# 05_PWMdriver.net
KiCad netlist of a schematic drawn in Altium Designer
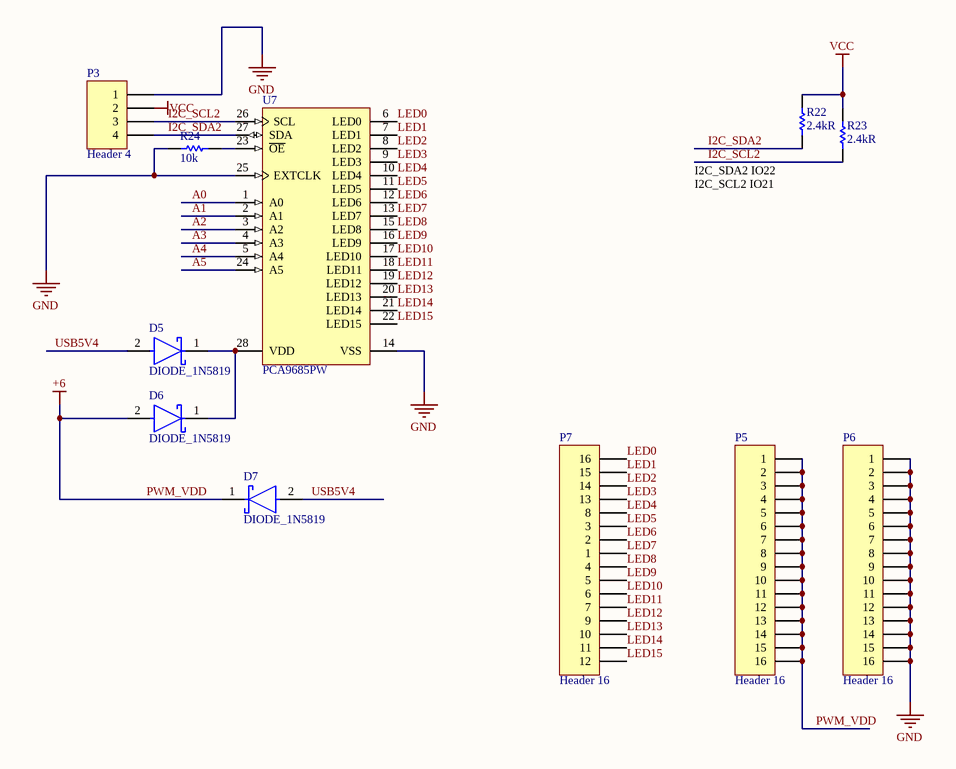
[diagram p0: 05_PWMdriver.SchDoc]

(export (version "E")
  (design (tool "Eeschema 10.0.6"))
  (components
    (comp (ref "D5")
      (value "DIODE_1N5819")
      (footprint "FP-SOD123-MFG")
      (description "DIODE SCHOTTKY 40V 1A SOD123")
      (fields
        (field (name "OCTOPART") "https://octopart.com/1n5819hw-7-f-diodes+inc.-323197")
        (field (name "MANUFACTURER") "Diodes Inc")
      )
      (libsource (lib "Altium Content Vault") (part "1d6ec82d83fb6aee721767c19dac4b9"))
    )
    (comp (ref "D6")
      (value "DIODE_1N5819")
      (footprint "FP-SOD123-MFG")
      (description "DIODE SCHOTTKY 40V 1A SOD123")
      (fields
        (field (name "OCTOPART") "https://octopart.com/1n5819hw-7-f-diodes+inc.-323197")
        (field (name "MANUFACTURER") "Diodes Inc")
      )
      (libsource (lib "Altium Content Vault") (part "1d6ec82d83fb6aee721767c19dac4b9"))
    )
    (comp (ref "D7")
      (value "DIODE_1N5819")
      (footprint "FP-SOD123-MFG")
      (description "DIODE SCHOTTKY 40V 1A SOD123")
      (fields
        (field (name "OCTOPART") "https://octopart.com/1n5819hw-7-f-diodes+inc.-323197")
        (field (name "MANUFACTURER") "Diodes Inc")
      )
      (libsource (lib "Altium Content Vault") (part "1d6ec82d83fb6aee721767c19dac4b9"))
    )
    (comp (ref "P3")
      (value "Header 4")
      (footprint "HDR1X4")
      (description "Header, 4-Pin")
      (fields (field (name "PUBLISHER") "Altium Limited"))
      (libsource (lib "Miscellaneous Connectors") (part "Header 4"))
    )
    (comp (ref "P5")
      (value "Header 16")
      (footprint "HDR1X16")
      (description "Header, 16-Pin")
      (fields (field (name "PUBLISHER") "Altium Limited"))
      (libsource (lib "Miscellaneous Connectors") (part "Header 16"))
    )
    (comp (ref "P6")
      (value "Header 16")
      (footprint "HDR1X16")
      (description "Header, 16-Pin")
      (fields (field (name "PUBLISHER") "Altium Limited"))
      (libsource (lib "Miscellaneous Connectors") (part "Header 16"))
    )
    (comp (ref "P7")
      (value "Header 16")
      (footprint "HDR1X16")
      (description "Header, 16-Pin")
      (fields (field (name "PUBLISHER") "Altium Limited"))
      (libsource (lib "") (part "Header 16_1"))
    )
    (comp (ref "R22")
      (value "2.4kR")
      (footprint "RESC1608X50X30ML20T20")
      (fields
        (field (name "PART NUMBER") "RR0816P-242-D")
        (field (name "MANUFACTURER") "Susumu")
        (field (name "Comment") "R0603_2.4K")
      )
      (libsource (lib "Altium Content Vault") (part "RES"))
    )
    (comp (ref "R23")
      (value "2.4kR")
      (footprint "RESC1608X50X30ML20T20")
      (fields
        (field (name "PART NUMBER") "RR0816P-242-D")
        (field (name "MANUFACTURER") "Susumu")
        (field (name "Comment") "R0603_2.4K")
      )
      (libsource (lib "Altium Content Vault") (part "RES"))
    )
    (comp (ref "R24")
      (value "10k")
      (footprint "RESC1609X55X30LL15T15")
      (description "Chip Resistor, 10 KOhm, +/- 1%, 0.1 W, -55 to 155 degC, 0603 (1608 Metric), RoHS, Tape and Reel")
      (fields (field (name "TOLERANCE") "1%") (field (name "MANUFACTURER") "Panasonic"))
      (libsource (lib "Altium Content Vault") (part "RES-2"))
    )
    (comp (ref "U7")
      (value "PCA9685PW")
      (footprint "SOT361-1_V")
      (fields (field (name "PARTNUMBER") "PCA9685"))
      (libsource (lib "Altium Content Vault") (part "NXP-PCA9685-SOT361-1"))
    )
  )
  (nets
    (net (code "1") (name "+6") (class "Default")
      (node (ref "D6") (pin "2") (pinfunction "A_2") (pintype "passive"))
      (node (ref "D7") (pin "1") (pinfunction "C_1") (pintype "passive"))
      (node (ref "P5") (pin "1") (pinfunction "1_1") (pintype "passive"))
      (node (ref "P5") (pin "10") (pinfunction "10_10") (pintype "passive"))
      (node (ref "P5") (pin "11") (pinfunction "11_11") (pintype "passive"))
      (node (ref "P5") (pin "12") (pinfunction "12_12") (pintype "passive"))
      (node (ref "P5") (pin "13") (pinfunction "13_13") (pintype "passive"))
      (node (ref "P5") (pin "14") (pinfunction "14_14") (pintype "passive"))
      (node (ref "P5") (pin "15") (pinfunction "15_15") (pintype "passive"))
      (node (ref "P5") (pin "16") (pinfunction "16_16") (pintype "passive"))
      (node (ref "P5") (pin "2") (pinfunction "2_2") (pintype "passive"))
      (node (ref "P5") (pin "3") (pinfunction "3_3") (pintype "passive"))
      (node (ref "P5") (pin "4") (pinfunction "4_4") (pintype "passive"))
      (node (ref "P5") (pin "5") (pinfunction "5_5") (pintype "passive"))
      (node (ref "P5") (pin "6") (pinfunction "6_6") (pintype "passive"))
      (node (ref "P5") (pin "7") (pinfunction "7_7") (pintype "passive"))
      (node (ref "P5") (pin "8") (pinfunction "8_8") (pintype "passive"))
      (node (ref "P5") (pin "9") (pinfunction "9_9") (pintype "passive"))
    )
    (net (code "2") (name "/A0") (class "Default")
      (node (ref "U7") (pin "1") (pinfunction "A0_1") (pintype "input"))
    )
    (net (code "3") (name "/A1") (class "Default")
      (node (ref "U7") (pin "2") (pinfunction "A1_2") (pintype "input"))
    )
    (net (code "4") (name "/A2") (class "Default")
      (node (ref "U7") (pin "3") (pinfunction "A2_3") (pintype "input"))
    )
    (net (code "5") (name "/A3") (class "Default")
      (node (ref "U7") (pin "4") (pinfunction "A3_4") (pintype "input"))
    )
    (net (code "6") (name "/A4") (class "Default")
      (node (ref "U7") (pin "5") (pinfunction "A4_5") (pintype "input"))
    )
    (net (code "7") (name "/A5") (class "Default")
      (node (ref "U7") (pin "24") (pinfunction "A5_24") (pintype "input"))
    )
    (net (code "8") (name "/I2C_SCL2") (class "Default")
      (node (ref "P3") (pin "3") (pinfunction "3_3") (pintype "passive"))
      (node (ref "R23") (pin "1") (pinfunction "1_1") (pintype "passive"))
      (node (ref "U7") (pin "26") (pinfunction "SCL_26") (pintype "input"))
    )
    (net (code "9") (name "/I2C_SDA2") (class "Default")
      (node (ref "P3") (pin "4") (pinfunction "4_4") (pintype "passive"))
      (node (ref "R22") (pin "1") (pinfunction "1_1") (pintype "passive"))
      (node (ref "U7") (pin "27") (pinfunction "SDA_27") (pintype "bidirectional"))
    )
    (net (code "10") (name "/LED0") (class "Default")
      (node (ref "P7") (pin "16") (pinfunction "16_16") (pintype "passive"))
      (node (ref "U7") (pin "6") (pinfunction "LED0_6") (pintype "tri_state"))
    )
    (net (code "11") (name "/LED1") (class "Default")
      (node (ref "P7") (pin "15") (pinfunction "15_15") (pintype "passive"))
      (node (ref "U7") (pin "7") (pinfunction "LED1_7") (pintype "tri_state"))
    )
    (net (code "12") (name "/LED2") (class "Default")
      (node (ref "P7") (pin "14") (pinfunction "14_14") (pintype "passive"))
      (node (ref "U7") (pin "8") (pinfunction "LED2_8") (pintype "tri_state"))
    )
    (net (code "13") (name "/LED3") (class "Default")
      (node (ref "P7") (pin "13") (pinfunction "13_13") (pintype "passive"))
      (node (ref "U7") (pin "9") (pinfunction "LED3_9") (pintype "tri_state"))
    )
    (net (code "14") (name "/LED4") (class "Default")
      (node (ref "P7") (pin "8") (pinfunction "8_8") (pintype "passive"))
      (node (ref "U7") (pin "10") (pinfunction "LED4_10") (pintype "tri_state"))
    )
    (net (code "15") (name "/LED5") (class "Default")
      (node (ref "P7") (pin "3") (pinfunction "3_3") (pintype "passive"))
      (node (ref "U7") (pin "11") (pinfunction "LED5_11") (pintype "tri_state"))
    )
    (net (code "16") (name "/LED6") (class "Default")
      (node (ref "P7") (pin "2") (pinfunction "2_2") (pintype "passive"))
      (node (ref "U7") (pin "12") (pinfunction "LED6_12") (pintype "tri_state"))
    )
    (net (code "17") (name "/LED7") (class "Default")
      (node (ref "P7") (pin "1") (pinfunction "1_1") (pintype "passive"))
      (node (ref "U7") (pin "13") (pinfunction "LED7_13") (pintype "tri_state"))
    )
    (net (code "18") (name "/LED8") (class "Default")
      (node (ref "P7") (pin "4") (pinfunction "4_4") (pintype "passive"))
      (node (ref "U7") (pin "15") (pinfunction "LED8_15") (pintype "tri_state"))
    )
    (net (code "19") (name "/LED9") (class "Default")
      (node (ref "P7") (pin "5") (pinfunction "5_5") (pintype "passive"))
      (node (ref "U7") (pin "16") (pinfunction "LED9_16") (pintype "tri_state"))
    )
    (net (code "20") (name "/LED10") (class "Default")
      (node (ref "P7") (pin "6") (pinfunction "6_6") (pintype "passive"))
      (node (ref "U7") (pin "17") (pinfunction "LED10_17") (pintype "tri_state"))
    )
    (net (code "21") (name "/LED11") (class "Default")
      (node (ref "P7") (pin "7") (pinfunction "7_7") (pintype "passive"))
      (node (ref "U7") (pin "18") (pinfunction "LED11_18") (pintype "tri_state"))
    )
    (net (code "22") (name "/LED12") (class "Default")
      (node (ref "P7") (pin "9") (pinfunction "9_9") (pintype "passive"))
      (node (ref "U7") (pin "19") (pinfunction "LED12_19") (pintype "tri_state"))
    )
    (net (code "23") (name "/LED13") (class "Default")
      (node (ref "P7") (pin "10") (pinfunction "10_10") (pintype "passive"))
      (node (ref "U7") (pin "20") (pinfunction "LED13_20") (pintype "tri_state"))
    )
    (net (code "24") (name "/LED14") (class "Default")
      (node (ref "P7") (pin "11") (pinfunction "11_11") (pintype "passive"))
      (node (ref "U7") (pin "21") (pinfunction "LED14_21") (pintype "tri_state"))
    )
    (net (code "25") (name "/LED15") (class "Default")
      (node (ref "P7") (pin "12") (pinfunction "12_12") (pintype "passive"))
      (node (ref "U7") (pin "22") (pinfunction "LED15_22") (pintype "tri_state"))
    )
    (net (code "26") (name "/USB5V4") (class "Default")
      (node (ref "D5") (pin "2") (pinfunction "A_2") (pintype "passive"))
      (node (ref "D7") (pin "2") (pinfunction "A_2") (pintype "passive"))
    )
    (net (code "27") (name "GND") (class "Default")
      (node (ref "P3") (pin "1") (pinfunction "1_1") (pintype "passive"))
      (node (ref "P6") (pin "1") (pinfunction "1_1") (pintype "passive"))
      (node (ref "P6") (pin "10") (pinfunction "10_10") (pintype "passive"))
      (node (ref "P6") (pin "11") (pinfunction "11_11") (pintype "passive"))
      (node (ref "P6") (pin "12") (pinfunction "12_12") (pintype "passive"))
      (node (ref "P6") (pin "13") (pinfunction "13_13") (pintype "passive"))
      (node (ref "P6") (pin "14") (pinfunction "14_14") (pintype "passive"))
      (node (ref "P6") (pin "15") (pinfunction "15_15") (pintype "passive"))
      (node (ref "P6") (pin "16") (pinfunction "16_16") (pintype "passive"))
      (node (ref "P6") (pin "2") (pinfunction "2_2") (pintype "passive"))
      (node (ref "P6") (pin "3") (pinfunction "3_3") (pintype "passive"))
      (node (ref "P6") (pin "4") (pinfunction "4_4") (pintype "passive"))
      (node (ref "P6") (pin "5") (pinfunction "5_5") (pintype "passive"))
      (node (ref "P6") (pin "6") (pinfunction "6_6") (pintype "passive"))
      (node (ref "P6") (pin "7") (pinfunction "7_7") (pintype "passive"))
      (node (ref "P6") (pin "8") (pinfunction "8_8") (pintype "passive"))
      (node (ref "P6") (pin "9") (pinfunction "9_9") (pintype "passive"))
      (node (ref "R24") (pin "2") (pinfunction "2_2") (pintype "passive"))
      (node (ref "U7") (pin "14") (pinfunction "VSS_14") (pintype "power_in"))
      (node (ref "U7") (pin "25") (pinfunction "EXTCLK_25") (pintype "input"))
    )
    (net (code "28") (name "Net-(D5-C)") (class "Default")
      (node (ref "D5") (pin "1") (pinfunction "C_1") (pintype "passive"))
      (node (ref "D6") (pin "1") (pinfunction "C_1") (pintype "passive"))
      (node (ref "U7") (pin "28") (pinfunction "VDD_28") (pintype "power_in"))
    )
    (net (code "29") (name "Net-(U7-~{OE})") (class "Default")
      (node (ref "R24") (pin "1") (pinfunction "1_1") (pintype "passive"))
      (node (ref "U7") (pin "23") (pinfunction "~{OE}_23") (pintype "input"))
    )
    (net (code "30") (name "VCC") (class "Default")
      (node (ref "P3") (pin "2") (pinfunction "2_2") (pintype "passive"))
      (node (ref "R22") (pin "2") (pinfunction "2_2") (pintype "passive"))
      (node (ref "R23") (pin "2") (pinfunction "2_2") (pintype "passive"))
    )
  )
)
